# motor5.net
KiCad netlist of a schematic drawn in EAGLE
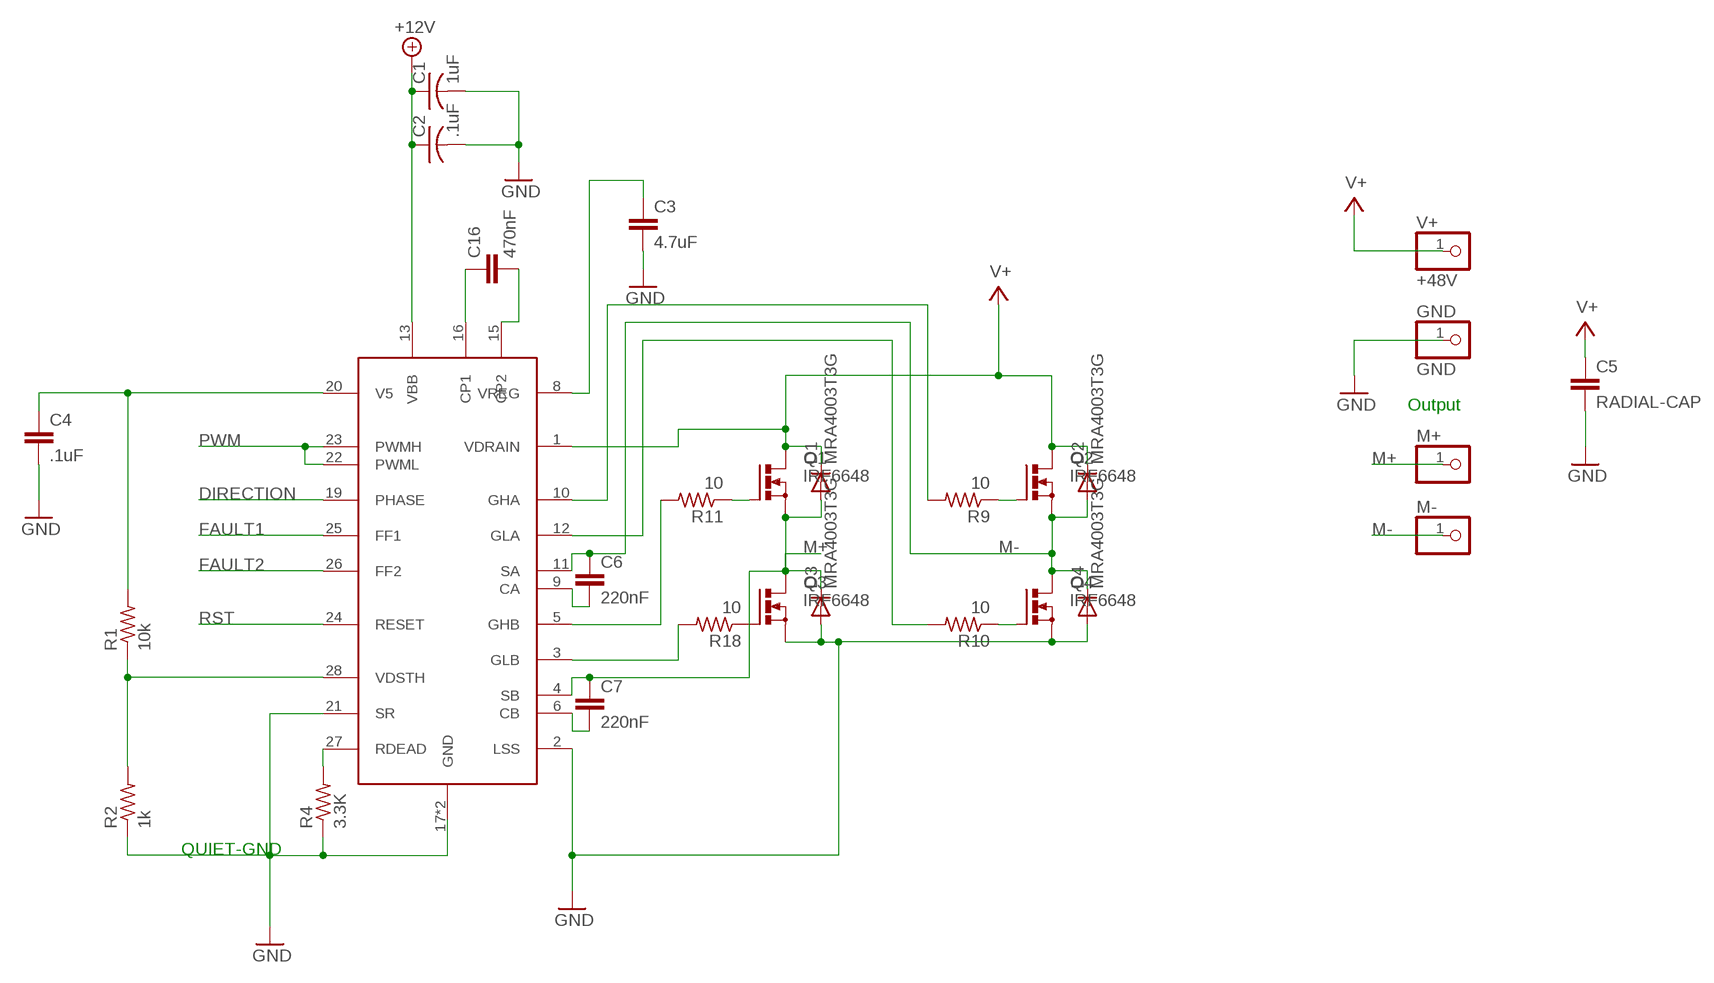
[diagram p0: schematic, sheet 1]
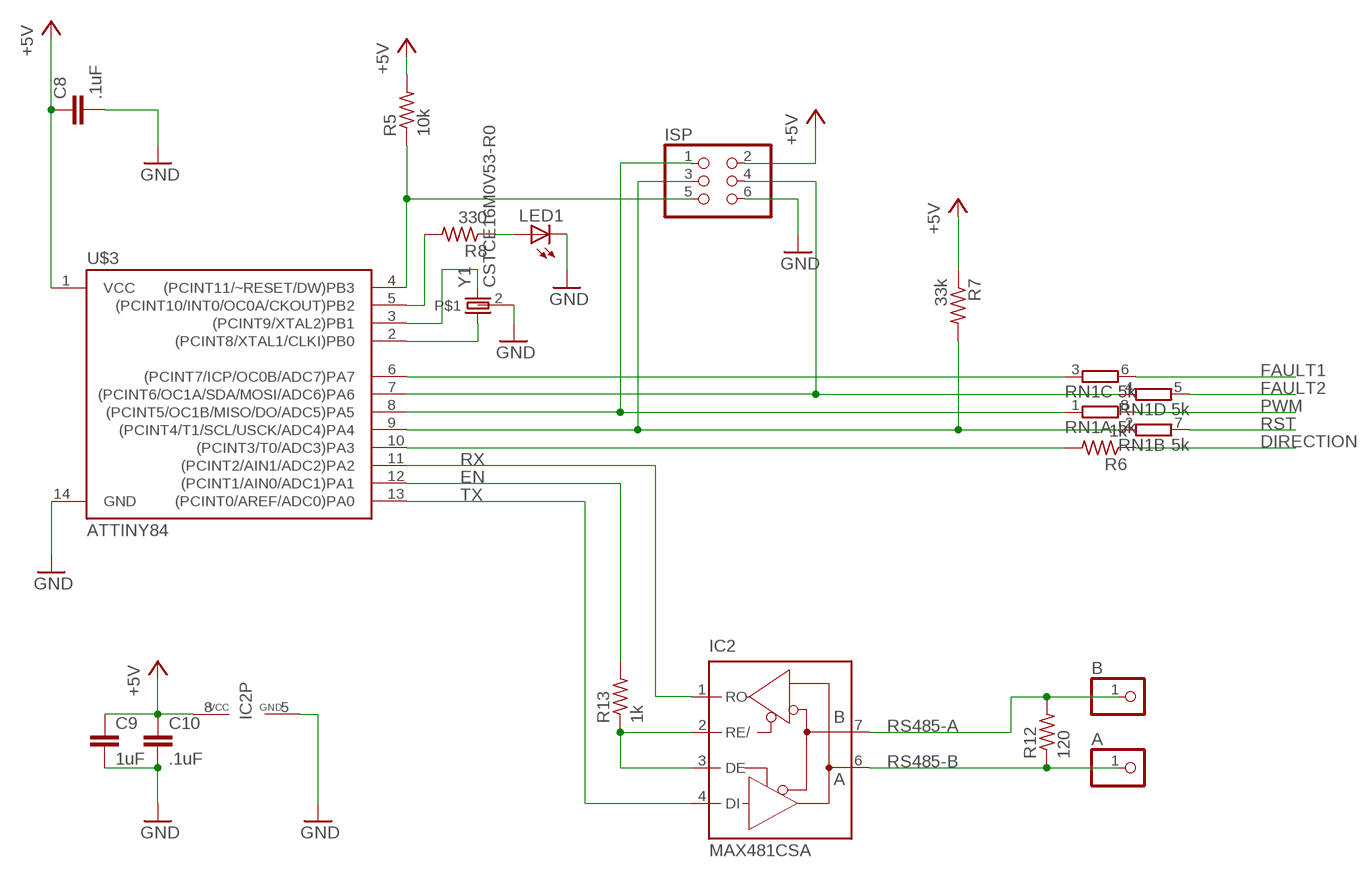
[diagram p1: schematic, sheet 2]
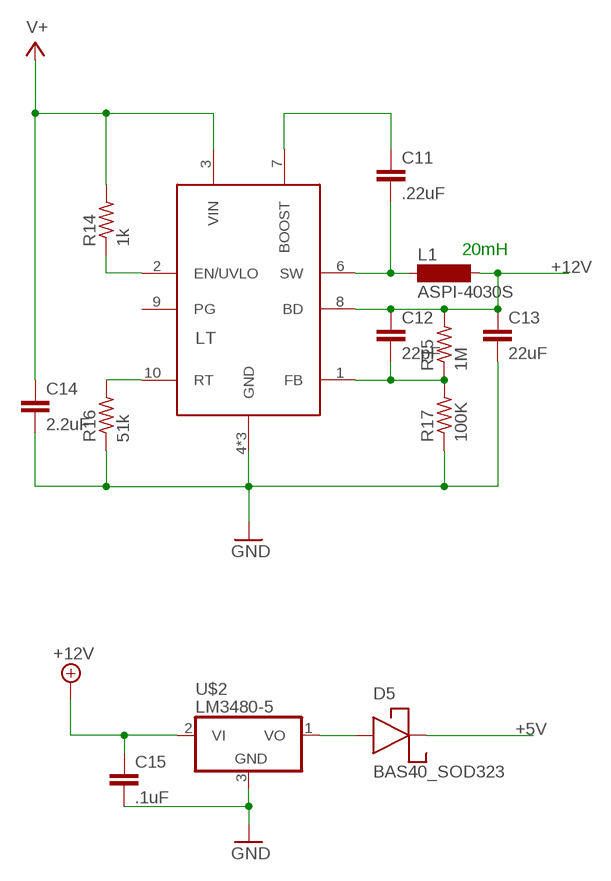
[diagram p2: schematic, sheet 3]

(export (version "E")
  (design (tool "Eeschema 10.0.6"))
  (components
    (comp (ref "C11")
      (value ".22uF")
      (footprint "eagle-import:C0603")
      (libsource (lib "eagle-import") (part "C-EUC0603"))
    )
    (comp (ref "C12")
      (value "22pF")
      (footprint "eagle-import:C0603")
      (libsource (lib "eagle-import") (part "C-EUC0603"))
    )
    (comp (ref "C13")
      (value "22uF")
      (footprint "eagle-import:C0805")
      (libsource (lib "eagle-import") (part "C-EUC0805"))
    )
    (comp (ref "C14")
      (value "2.2uF")
      (footprint "eagle-import:C0603")
      (libsource (lib "eagle-import") (part "C-EUC0603"))
    )
    (comp (ref "C15")
      (value ".1uF")
      (footprint "eagle-import:C0603")
      (libsource (lib "eagle-import") (part "C-EUC0603"))
    )
    (comp (ref "D5")
      (value "BAS40_SOD323")
      (footprint "eagle-import:SOD323")
      (libsource (lib "eagle-import") (part "BAS40_SOD323"))
    )
    (comp (ref "L1")
      (value "ASPI-4030S")
      (footprint "eagle-import:ASPI-4030S")
      (libsource (lib "eagle-import") (part "ASPI-4030S"))
    )
    (comp (ref "LT")
      (value "LT3990")
      (footprint "eagle-import:DFN10-3X3")
      (libsource (lib "eagle-import") (part "LT3990"))
    )
    (comp (ref "R14")
      (value "1k")
      (footprint "eagle-import:R0603")
      (libsource (lib "eagle-import") (part "R-US_R0603"))
    )
    (comp (ref "R15")
      (value "1M")
      (footprint "eagle-import:R0603")
      (libsource (lib "eagle-import") (part "R-US_R0603"))
    )
    (comp (ref "R16")
      (value "51k")
      (footprint "eagle-import:R0603")
      (libsource (lib "eagle-import") (part "R-US_R0603"))
    )
    (comp (ref "R17")
      (value "100K")
      (footprint "eagle-import:R0603")
      (libsource (lib "eagle-import") (part "R-US_R0603"))
    )
    (comp (ref "U$2")
      (value "LM3480-5")
      (footprint "eagle-import:SOT23")
      (libsource (lib "eagle-import") (part "LM3480-5"))
    )
    (comp (ref "A")
      (value "PINHD-1X1")
      (footprint "eagle-import:1X01")
      (libsource (lib "eagle-import") (part "PINHD-1X1"))
    )
    (comp (ref "B")
      (value "PINHD-1X1")
      (footprint "eagle-import:1X01")
      (libsource (lib "eagle-import") (part "PINHD-1X1"))
    )
    (comp (ref "C8")
      (value ".1uF")
      (footprint "eagle-import:C0603")
      (libsource (lib "eagle-import") (part "C-EUC0603"))
    )
    (comp (ref "C9")
      (value "1uF")
      (footprint "eagle-import:C0603")
      (libsource (lib "eagle-import") (part "C-EUC0603"))
    )
    (comp (ref "C10")
      (value ".1uF")
      (footprint "eagle-import:C0603")
      (libsource (lib "eagle-import") (part "C-EUC0603"))
    )
    (comp (ref "IC2")
      (value "MAX481CSA")
      (footprint "eagle-import:SO08")
      (fields (field (name "MF") "MAXIM"))
      (libsource (lib "eagle-import") (part "MAX481CSA"))
    )
    (comp (ref "ISP")
      (value "PINHD-2X3")
      (footprint "eagle-import:2X03")
      (libsource (lib "eagle-import") (part "PINHD-2X3"))
    )
    (comp (ref "LED1")
      (value "LEDCHIPLED_0603")
      (footprint "eagle-import:CHIPLED_0603")
      (libsource (lib "eagle-import") (part "LEDCHIPLED_0603"))
    )
    (comp (ref "R5")
      (value "10k")
      (footprint "eagle-import:R0603")
      (libsource (lib "eagle-import") (part "R-US_R0603"))
    )
    (comp (ref "R6")
      (value "1k")
      (footprint "eagle-import:R0603")
      (libsource (lib "eagle-import") (part "R-US_R0603"))
    )
    (comp (ref "R7")
      (value "33k")
      (footprint "eagle-import:R0603")
      (libsource (lib "eagle-import") (part "R-US_R0603"))
    )
    (comp (ref "R8")
      (value "330")
      (footprint "eagle-import:R0603")
      (libsource (lib "eagle-import") (part "R-US_R0603"))
    )
    (comp (ref "R12")
      (value "120")
      (footprint "eagle-import:R0603")
      (libsource (lib "eagle-import") (part "R-US_R0603"))
    )
    (comp (ref "R13")
      (value "1k")
      (footprint "eagle-import:R0603")
      (libsource (lib "eagle-import") (part "R-US_R0603"))
    )
    (comp (ref "RN1")
      (value "5k")
      (footprint "eagle-import:EXB38V")
      (libsource (lib "eagle-import") (part "4R-NEXB38V"))
    )
    (comp (ref "U$3")
      (value "ATTINY84")
      (footprint "eagle-import:SO14")
      (libsource (lib "eagle-import") (part "ATTINY84"))
    )
    (comp (ref "Y1")
      (value "CSTCE16M0V53-R0")
      (footprint "eagle-import:MYSMD2_RESONATOR")
      (libsource (lib "eagle-import") (part "CSTCE16M0V53-R0"))
    )
    (comp (ref "ALLGR")
      (value "ALLEGRO-A3921")
      (footprint "eagle-import:TSSOP28")
      (libsource (lib "eagle-import") (part "ALLEGRO-A3921"))
    )
    (comp (ref "C1")
      (value "1uF")
      (footprint "eagle-import:C0603")
      (libsource (lib "eagle-import") (part "C-USC0603"))
    )
    (comp (ref "C2")
      (value ".1uF")
      (footprint "eagle-import:C0603")
      (libsource (lib "eagle-import") (part "C-USC0603"))
    )
    (comp (ref "C3")
      (value "4.7uF")
      (footprint "eagle-import:C0603")
      (libsource (lib "eagle-import") (part "C-EUC0603"))
    )
    (comp (ref "C4")
      (value ".1uF")
      (footprint "eagle-import:C0603")
      (libsource (lib "eagle-import") (part "C-EUC0603"))
    )
    (comp (ref "C5")
      (value "RADIAL-CAP")
      (footprint "eagle-import:RADIAL-CAP")
      (libsource (lib "eagle-import") (part "RADIAL-CAP"))
    )
    (comp (ref "C6")
      (value "220nF")
      (footprint "eagle-import:C0603")
      (libsource (lib "eagle-import") (part "C-EUC0603"))
    )
    (comp (ref "C7")
      (value "220nF")
      (footprint "eagle-import:C0603")
      (libsource (lib "eagle-import") (part "C-EUC0603"))
    )
    (comp (ref "C16")
      (value "470nF")
      (footprint "eagle-import:C0603")
      (libsource (lib "eagle-import") (part "C-EUC0603"))
    )
    (comp (ref "D1")
      (value "MRA4003T3G")
      (footprint "eagle-import:SMA")
      (libsource (lib "eagle-import") (part "MRA4003T3G"))
    )
    (comp (ref "D2")
      (value "MRA4003T3G")
      (footprint "eagle-import:SMA")
      (libsource (lib "eagle-import") (part "MRA4003T3G"))
    )
    (comp (ref "D3")
      (value "MRA4003T3G")
      (footprint "eagle-import:SMA")
      (libsource (lib "eagle-import") (part "MRA4003T3G"))
    )
    (comp (ref "D4")
      (value "MRA4003T3G")
      (footprint "eagle-import:SMA")
      (libsource (lib "eagle-import") (part "MRA4003T3G"))
    )
    (comp (ref "GND")
      (value "GND")
      (footprint "eagle-import:1X01")
      (libsource (lib "eagle-import") (part "PINHD-1X1"))
    )
    (comp (ref "M+")
      (value "PINHD-1X1")
      (footprint "eagle-import:1X01")
      (libsource (lib "eagle-import") (part "PINHD-1X1"))
    )
    (comp (ref "M-")
      (value "PINHD-1X1")
      (footprint "eagle-import:1X01")
      (libsource (lib "eagle-import") (part "PINHD-1X1"))
    )
    (comp (ref "Q1")
      (value "IRF6648")
      (footprint "eagle-import:DIRECTFET")
      (libsource (lib "eagle-import") (part "IRF6648"))
    )
    (comp (ref "Q2")
      (value "IRF6648")
      (footprint "eagle-import:DIRECTFET")
      (libsource (lib "eagle-import") (part "IRF6648"))
    )
    (comp (ref "Q3")
      (value "IRF6648")
      (footprint "eagle-import:DIRECTFET")
      (libsource (lib "eagle-import") (part "IRF6648"))
    )
    (comp (ref "Q4")
      (value "IRF6648")
      (footprint "eagle-import:DIRECTFET")
      (libsource (lib "eagle-import") (part "IRF6648"))
    )
    (comp (ref "R1")
      (value "10k")
      (footprint "eagle-import:R0603")
      (libsource (lib "eagle-import") (part "R-US_R0603"))
    )
    (comp (ref "R2")
      (value "1k")
      (footprint "eagle-import:R0603")
      (libsource (lib "eagle-import") (part "R-US_R0603"))
    )
    (comp (ref "R4")
      (value "3.3K")
      (footprint "eagle-import:R0603")
      (libsource (lib "eagle-import") (part "R-US_R0603"))
    )
    (comp (ref "R9")
      (value "10")
      (footprint "eagle-import:R0603")
      (libsource (lib "eagle-import") (part "R-US_R0603"))
    )
    (comp (ref "R10")
      (value "10")
      (footprint "eagle-import:R0603")
      (libsource (lib "eagle-import") (part "R-US_R0603"))
    )
    (comp (ref "R11")
      (value "10")
      (footprint "eagle-import:R0603")
      (libsource (lib "eagle-import") (part "R-US_R0603"))
    )
    (comp (ref "R18")
      (value "10")
      (footprint "eagle-import:R0603")
      (libsource (lib "eagle-import") (part "R-US_R0603"))
    )
    (comp (ref "V+")
      (value "+48V")
      (footprint "eagle-import:1X01")
      (libsource (lib "eagle-import") (part "PINHD-1X1"))
    )
  )
  (nets
    (net (code "1") (name "+5V") (class "Default")
      (node (ref "C10") (pin "1") (pinfunction "1_1") (pintype "passive"))
      (node (ref "C8") (pin "1") (pinfunction "1_1") (pintype "passive"))
      (node (ref "C9") (pin "1") (pinfunction "1_1") (pintype "passive"))
      (node (ref "D5") (pin "1") (pinfunction "P$2_1") (pintype "bidirectional"))
      (node (ref "IC2") (pin "8") (pinfunction "VCC_8") (pintype "power_in"))
      (node (ref "ISP") (pin "2") (pinfunction "2_2") (pintype "passive"))
      (node (ref "R5") (pin "2") (pinfunction "2_2") (pintype "passive"))
      (node (ref "R7") (pin "1") (pinfunction "1_1") (pintype "passive"))
      (node (ref "U$3") (pin "1") (pinfunction "VCC_1") (pintype "bidirectional"))
    )
    (net (code "2") (name "+12V") (class "Default")
      (node (ref "ALLGR") (pin "13") (pinfunction "VBB_13") (pintype "bidirectional"))
      (node (ref "C1") (pin "1") (pinfunction "1_1") (pintype "passive"))
      (node (ref "C12") (pin "1") (pinfunction "1_1") (pintype "passive"))
      (node (ref "C13") (pin "1") (pinfunction "1_1") (pintype "passive"))
      (node (ref "C15") (pin "1") (pinfunction "1_1") (pintype "passive"))
      (node (ref "C2") (pin "1") (pinfunction "1_1") (pintype "passive"))
      (node (ref "L1") (pin "P$2") (pinfunction "2_P$2") (pintype "passive"))
      (node (ref "LT") (pin "8") (pinfunction "BD_8") (pintype "bidirectional"))
      (node (ref "R15") (pin "2") (pinfunction "2_2") (pintype "passive"))
      (node (ref "U$2") (pin "2") (pinfunction "VI_2") (pintype "input"))
    )
    (net (code "3") (name "DIRECTION") (class "Default")
      (node (ref "ALLGR") (pin "19") (pinfunction "PHASE_19") (pintype "bidirectional"))
      (node (ref "R6") (pin "1") (pinfunction "1_1") (pintype "passive"))
    )
    (net (code "4") (name "EN") (class "Default")
      (node (ref "R13") (pin "2") (pinfunction "2_2") (pintype "passive"))
      (node (ref "U$3") (pin "12") (pinfunction "(PCINT1/AIN0/ADC1)PA1_12") (pintype "bidirectional"))
    )
    (net (code "5") (name "FAULT1") (class "Default")
      (node (ref "ALLGR") (pin "25") (pinfunction "FF1_25") (pintype "bidirectional"))
      (node (ref "RN1") (pin "6") (pinfunction "2_6") (pintype "passive"))
    )
    (net (code "6") (name "FAULT2") (class "Default")
      (node (ref "ALLGR") (pin "26") (pinfunction "FF2_26") (pintype "bidirectional"))
      (node (ref "RN1") (pin "5") (pinfunction "2_5") (pintype "passive"))
    )
    (net (code "7") (name "GND") (class "Default")
      (node (ref "ALLGR") (pin "17") (pinfunction "GND_17") (pintype "bidirectional"))
      (node (ref "ALLGR") (pin "2") (pinfunction "LSS_2") (pintype "bidirectional"))
      (node (ref "ALLGR") (pin "21") (pinfunction "SR_21") (pintype "bidirectional"))
      (node (ref "ALLGR") (pin "P$1") (pinfunction "GND_P$1") (pintype "bidirectional"))
      (node (ref "C1") (pin "2") (pinfunction "2_2") (pintype "passive"))
      (node (ref "C10") (pin "2") (pinfunction "2_2") (pintype "passive"))
      (node (ref "C13") (pin "2") (pinfunction "2_2") (pintype "passive"))
      (node (ref "C14") (pin "2") (pinfunction "2_2") (pintype "passive"))
      (node (ref "C15") (pin "2") (pinfunction "2_2") (pintype "passive"))
      (node (ref "C2") (pin "2") (pinfunction "2_2") (pintype "passive"))
      (node (ref "C3") (pin "2") (pinfunction "2_2") (pintype "passive"))
      (node (ref "C4") (pin "2") (pinfunction "2_2") (pintype "passive"))
      (node (ref "C5") (pin "P$2") (pinfunction "2_P$2") (pintype "passive"))
      (node (ref "C8") (pin "2") (pinfunction "2_2") (pintype "passive"))
      (node (ref "C9") (pin "2") (pinfunction "2_2") (pintype "passive"))
      (node (ref "D3") (pin "A") (pinfunction "A_A") (pintype "passive"))
      (node (ref "D4") (pin "A") (pinfunction "A_A") (pintype "passive"))
      (node (ref "GND") (pin "1") (pinfunction "1_1") (pintype "passive"))
      (node (ref "IC2") (pin "5") (pinfunction "GND_5") (pintype "power_in"))
      (node (ref "ISP") (pin "6") (pinfunction "6_6") (pintype "passive"))
      (node (ref "LED1") (pin "C") (pinfunction "C_C") (pintype "passive"))
      (node (ref "LT") (pin "4") (pinfunction "GND_4") (pintype "bidirectional"))
      (node (ref "LT") (pin "5") (pinfunction "GND_5") (pintype "bidirectional"))
      (node (ref "LT") (pin "EXP") (pinfunction "GND_EXP") (pintype "bidirectional"))
      (node (ref "Q3") (pin "S@1") (pinfunction "S_S@1") (pintype "passive"))
      (node (ref "Q3") (pin "S@2") (pinfunction "S_S@2") (pintype "passive"))
      (node (ref "Q4") (pin "S@1") (pinfunction "S_S@1") (pintype "passive"))
      (node (ref "Q4") (pin "S@2") (pinfunction "S_S@2") (pintype "passive"))
      (node (ref "R16") (pin "1") (pinfunction "1_1") (pintype "passive"))
      (node (ref "R17") (pin "1") (pinfunction "1_1") (pintype "passive"))
      (node (ref "R2") (pin "1") (pinfunction "1_1") (pintype "passive"))
      (node (ref "R4") (pin "1") (pinfunction "1_1") (pintype "passive"))
      (node (ref "U$2") (pin "3") (pinfunction "GND_3") (pintype "input"))
      (node (ref "U$3") (pin "14") (pinfunction "GND_14") (pintype "bidirectional"))
      (node (ref "Y1") (pin "2") (pinfunction "P$1_2") (pintype "bidirectional"))
    )
    (net (code "8") (name "M+") (class "Default")
      (node (ref "ALLGR") (pin "4") (pinfunction "SB_4") (pintype "bidirectional"))
      (node (ref "C7") (pin "1") (pinfunction "1_1") (pintype "passive"))
      (node (ref "D1") (pin "A") (pinfunction "A_A") (pintype "passive"))
      (node (ref "D3") (pin "C") (pinfunction "C_C") (pintype "passive"))
      (node (ref "M+") (pin "1") (pinfunction "1_1") (pintype "passive"))
      (node (ref "Q1") (pin "S@1") (pinfunction "S_S@1") (pintype "passive"))
      (node (ref "Q1") (pin "S@2") (pinfunction "S_S@2") (pintype "passive"))
      (node (ref "Q3") (pin "D@1") (pinfunction "D_D@1") (pintype "passive"))
      (node (ref "Q3") (pin "D@2") (pinfunction "D_D@2") (pintype "passive"))
      (node (ref "Q3") (pin "D@3") (pinfunction "D_D@3") (pintype "passive"))
      (node (ref "Q3") (pin "D@4") (pinfunction "D_D@4") (pintype "passive"))
    )
    (net (code "9") (name "M-") (class "Default")
      (node (ref "ALLGR") (pin "11") (pinfunction "SA_11") (pintype "bidirectional"))
      (node (ref "C6") (pin "1") (pinfunction "1_1") (pintype "passive"))
      (node (ref "D2") (pin "A") (pinfunction "A_A") (pintype "passive"))
      (node (ref "D4") (pin "C") (pinfunction "C_C") (pintype "passive"))
      (node (ref "M-") (pin "1") (pinfunction "1_1") (pintype "passive"))
      (node (ref "Q2") (pin "S@1") (pinfunction "S_S@1") (pintype "passive"))
      (node (ref "Q2") (pin "S@2") (pinfunction "S_S@2") (pintype "passive"))
      (node (ref "Q4") (pin "D@1") (pinfunction "D_D@1") (pintype "passive"))
      (node (ref "Q4") (pin "D@2") (pinfunction "D_D@2") (pintype "passive"))
      (node (ref "Q4") (pin "D@3") (pinfunction "D_D@3") (pintype "passive"))
      (node (ref "Q4") (pin "D@4") (pinfunction "D_D@4") (pintype "passive"))
    )
    (net (code "10") (name "Net-(ALLGR-CA)") (class "Default")
      (node (ref "ALLGR") (pin "9") (pinfunction "CA_9") (pintype "bidirectional"))
      (node (ref "C6") (pin "2") (pinfunction "2_2") (pintype "passive"))
    )
    (net (code "11") (name "Net-(ALLGR-CB)") (class "Default")
      (node (ref "ALLGR") (pin "6") (pinfunction "CB_6") (pintype "bidirectional"))
      (node (ref "C7") (pin "2") (pinfunction "2_2") (pintype "passive"))
    )
    (net (code "12") (name "Net-(ALLGR-CP1)") (class "Default")
      (node (ref "ALLGR") (pin "16") (pinfunction "CP1_16") (pintype "bidirectional"))
      (node (ref "C16") (pin "1") (pinfunction "1_1") (pintype "passive"))
    )
    (net (code "13") (name "Net-(ALLGR-CP2)") (class "Default")
      (node (ref "ALLGR") (pin "15") (pinfunction "CP2_15") (pintype "bidirectional"))
      (node (ref "C16") (pin "2") (pinfunction "2_2") (pintype "passive"))
    )
    (net (code "14") (name "Net-(ALLGR-GHA)") (class "Default")
      (node (ref "ALLGR") (pin "10") (pinfunction "GHA_10") (pintype "bidirectional"))
      (node (ref "R9") (pin "2") (pinfunction "2_2") (pintype "passive"))
    )
    (net (code "15") (name "Net-(ALLGR-GHB)") (class "Default")
      (node (ref "ALLGR") (pin "5") (pinfunction "GHB_5") (pintype "bidirectional"))
      (node (ref "R11") (pin "2") (pinfunction "2_2") (pintype "passive"))
    )
    (net (code "16") (name "Net-(ALLGR-GLA)") (class "Default")
      (node (ref "ALLGR") (pin "12") (pinfunction "GLA_12") (pintype "bidirectional"))
      (node (ref "R10") (pin "2") (pinfunction "2_2") (pintype "passive"))
    )
    (net (code "17") (name "Net-(ALLGR-GLB)") (class "Default")
      (node (ref "ALLGR") (pin "3") (pinfunction "GLB_3") (pintype "bidirectional"))
      (node (ref "R18") (pin "2") (pinfunction "2_2") (pintype "passive"))
    )
    (net (code "18") (name "Net-(ALLGR-RDEAD)") (class "Default")
      (node (ref "ALLGR") (pin "27") (pinfunction "RDEAD_27") (pintype "bidirectional"))
      (node (ref "R4") (pin "2") (pinfunction "2_2") (pintype "passive"))
    )
    (net (code "19") (name "Net-(ALLGR-V5)") (class "Default")
      (node (ref "ALLGR") (pin "20") (pinfunction "V5_20") (pintype "bidirectional"))
      (node (ref "C4") (pin "1") (pinfunction "1_1") (pintype "passive"))
      (node (ref "R1") (pin "2") (pinfunction "2_2") (pintype "passive"))
    )
    (net (code "20") (name "Net-(ALLGR-VDSTH)") (class "Default")
      (node (ref "ALLGR") (pin "28") (pinfunction "VDSTH_28") (pintype "bidirectional"))
      (node (ref "R1") (pin "1") (pinfunction "1_1") (pintype "passive"))
      (node (ref "R2") (pin "2") (pinfunction "2_2") (pintype "passive"))
    )
    (net (code "21") (name "Net-(ALLGR-VREG)") (class "Default")
      (node (ref "ALLGR") (pin "8") (pinfunction "VREG_8") (pintype "bidirectional"))
      (node (ref "C3") (pin "1") (pinfunction "1_1") (pintype "passive"))
    )
    (net (code "22") (name "Net-(D5-P$1)") (class "Default")
      (node (ref "D5") (pin "2") (pinfunction "P$1_2") (pintype "bidirectional"))
      (node (ref "U$2") (pin "1") (pinfunction "VO_1") (pintype "passive"))
    )
    (net (code "23") (name "Net-(IC2A-DE)") (class "Default")
      (node (ref "IC2") (pin "2") (pinfunction "RE/_2") (pintype "input"))
      (node (ref "IC2") (pin "3") (pinfunction "DE_3") (pintype "input"))
      (node (ref "R13") (pin "1") (pinfunction "1_1") (pintype "passive"))
    )
    (net (code "24") (name "Net-(L1-1)") (class "Default")
      (node (ref "C11") (pin "2") (pinfunction "2_2") (pintype "passive"))
      (node (ref "L1") (pin "P$1") (pinfunction "1_P$1") (pintype "passive"))
      (node (ref "LT") (pin "6") (pinfunction "SW_6") (pintype "bidirectional"))
    )
    (net (code "25") (name "Net-(LED1-PadA)") (class "Default")
      (node (ref "LED1") (pin "A") (pinfunction "A_A") (pintype "passive"))
      (node (ref "R8") (pin "1") (pinfunction "1_1") (pintype "passive"))
    )
    (net (code "26") (name "Net-(LT-BOOST)") (class "Default")
      (node (ref "C11") (pin "1") (pinfunction "1_1") (pintype "passive"))
      (node (ref "LT") (pin "7") (pinfunction "BOOST_7") (pintype "bidirectional"))
    )
    (net (code "27") (name "Net-(LT-EN{slash}UVLO)") (class "Default")
      (node (ref "LT") (pin "2") (pinfunction "EN/UVLO_2") (pintype "bidirectional"))
      (node (ref "R14") (pin "1") (pinfunction "1_1") (pintype "passive"))
    )
    (net (code "28") (name "Net-(LT-FB)") (class "Default")
      (node (ref "C12") (pin "2") (pinfunction "2_2") (pintype "passive"))
      (node (ref "LT") (pin "1") (pinfunction "FB_1") (pintype "bidirectional"))
      (node (ref "R15") (pin "1") (pinfunction "1_1") (pintype "passive"))
      (node (ref "R17") (pin "2") (pinfunction "2_2") (pintype "passive"))
    )
    (net (code "29") (name "Net-(LT-RT)") (class "Default")
      (node (ref "LT") (pin "10") (pinfunction "RT_10") (pintype "bidirectional"))
      (node (ref "R16") (pin "2") (pinfunction "2_2") (pintype "passive"))
    )
    (net (code "30") (name "Net-(Q1-PadG)") (class "Default")
      (node (ref "Q1") (pin "G") (pinfunction "G_G") (pintype "passive"))
      (node (ref "R11") (pin "1") (pinfunction "1_1") (pintype "passive"))
    )
    (net (code "31") (name "Net-(Q2-PadG)") (class "Default")
      (node (ref "Q2") (pin "G") (pinfunction "G_G") (pintype "passive"))
      (node (ref "R9") (pin "1") (pinfunction "1_1") (pintype "passive"))
    )
    (net (code "32") (name "Net-(Q3-PadG)") (class "Default")
      (node (ref "Q3") (pin "G") (pinfunction "G_G") (pintype "passive"))
      (node (ref "R18") (pin "1") (pinfunction "1_1") (pintype "passive"))
    )
    (net (code "33") (name "Net-(Q4-PadG)") (class "Default")
      (node (ref "Q4") (pin "G") (pinfunction "G_G") (pintype "passive"))
      (node (ref "R10") (pin "1") (pinfunction "1_1") (pintype "passive"))
    )
    (net (code "34") (name "Net-(RN1B-1)") (class "Default")
      (node (ref "ISP") (pin "3") (pinfunction "3_3") (pintype "passive"))
      (node (ref "R7") (pin "2") (pinfunction "2_2") (pintype "passive"))
      (node (ref "RN1") (pin "2") (pinfunction "1_2") (pintype "passive"))
      (node (ref "U$3") (pin "9") (pinfunction "(PCINT4/T1/SCL/USCK/ADC4)PA4_9") (pintype "bidirectional"))
    )
    (net (code "35") (name "Net-(RN1C-1)") (class "Default")
      (node (ref "RN1") (pin "3") (pinfunction "1_3") (pintype "passive"))
      (node (ref "U$3") (pin "6") (pinfunction "(PCINT7/ICP/OC0B/ADC7)PA7_6") (pintype "bidirectional"))
    )
    (net (code "36") (name "Net-(RN1D-1)") (class "Default")
      (node (ref "ISP") (pin "4") (pinfunction "4_4") (pintype "passive"))
      (node (ref "RN1") (pin "4") (pinfunction "1_4") (pintype "passive"))
      (node (ref "U$3") (pin "7") (pinfunction "(PCINT6/OC1A/SDA/MOSI/ADC6)PA6_7") (pintype "bidirectional"))
    )
    (net (code "37") (name "Net-(U$3-(PCINT3{slash}T0{slash}ADC3)PA3)") (class "Default")
      (node (ref "R6") (pin "2") (pinfunction "2_2") (pintype "passive"))
      (node (ref "U$3") (pin "10") (pinfunction "(PCINT3/T0/ADC3)PA3_10") (pintype "bidirectional"))
    )
    (net (code "38") (name "Net-(U$3-(PCINT5{slash}OC1B{slash}MISO{slash}DO{slash}ADC5)PA5)") (class "Default")
      (node (ref "ISP") (pin "1") (pinfunction "1_1") (pintype "passive"))
      (node (ref "RN1") (pin "1") (pinfunction "1_1") (pintype "passive"))
      (node (ref "U$3") (pin "8") (pinfunction "(PCINT5/OC1B/MISO/DO/ADC5)PA5_8") (pintype "bidirectional"))
    )
    (net (code "39") (name "Net-(U$3-(PCINT8{slash}XTAL1{slash}CLKI)PB0)") (class "Default")
      (node (ref "U$3") (pin "2") (pinfunction "(PCINT8/XTAL1/CLKI)PB0_2") (pintype "bidirectional"))
      (node (ref "Y1") (pin "1") (pinfunction "1_1") (pintype "passive"))
    )
    (net (code "40") (name "Net-(U$3-(PCINT9{slash}XTAL2)PB1)") (class "Default")
      (node (ref "U$3") (pin "3") (pinfunction "(PCINT9/XTAL2)PB1_3") (pintype "bidirectional"))
      (node (ref "Y1") (pin "3") (pinfunction "2_3") (pintype "passive"))
    )
    (net (code "41") (name "Net-(U$3-(PCINT10{slash}INT0{slash}OC0A{slash}CKOUT)PB2)") (class "Default")
      (node (ref "R8") (pin "2") (pinfunction "2_2") (pintype "passive"))
      (node (ref "U$3") (pin "5") (pinfunction "(PCINT10/INT0/OC0A/CKOUT)PB2_5") (pintype "bidirectional"))
    )
    (net (code "42") (name "Net-(U$3-(PCINT11{slash}~{RESET{slash}DW})PB3)") (class "Default")
      (node (ref "ISP") (pin "5") (pinfunction "5_5") (pintype "passive"))
      (node (ref "R5") (pin "1") (pinfunction "1_1") (pintype "passive"))
      (node (ref "U$3") (pin "4") (pinfunction "(PCINT11/~{RESET/DW})PB3_4") (pintype "bidirectional"))
    )
    (net (code "43") (name "PWM") (class "Default")
      (node (ref "ALLGR") (pin "22") (pinfunction "PWML_22") (pintype "bidirectional"))
      (node (ref "ALLGR") (pin "23") (pinfunction "PWMH_23") (pintype "bidirectional"))
      (node (ref "RN1") (pin "8") (pinfunction "2_8") (pintype "passive"))
    )
    (net (code "44") (name "RS485-A") (class "Default")
      (node (ref "B") (pin "1") (pinfunction "1_1") (pintype "passive"))
      (node (ref "IC2") (pin "7") (pinfunction "B_7") (pintype "passive"))
      (node (ref "R12") (pin "2") (pinfunction "2_2") (pintype "passive"))
    )
    (net (code "45") (name "RS485-B") (class "Default")
      (node (ref "A") (pin "1") (pinfunction "1_1") (pintype "passive"))
      (node (ref "IC2") (pin "6") (pinfunction "A_6") (pintype "passive"))
      (node (ref "R12") (pin "1") (pinfunction "1_1") (pintype "passive"))
    )
    (net (code "46") (name "RST") (class "Default")
      (node (ref "ALLGR") (pin "24") (pinfunction "RESET_24") (pintype "bidirectional"))
      (node (ref "RN1") (pin "7") (pinfunction "2_7") (pintype "passive"))
    )
    (net (code "47") (name "RX") (class "Default")
      (node (ref "IC2") (pin "1") (pinfunction "RO_1") (pintype "output"))
      (node (ref "U$3") (pin "11") (pinfunction "(PCINT2/AIN1/ADC2)PA2_11") (pintype "bidirectional"))
    )
    (net (code "48") (name "TX") (class "Default")
      (node (ref "IC2") (pin "4") (pinfunction "DI_4") (pintype "input"))
      (node (ref "U$3") (pin "13") (pinfunction "(PCINT0/AREF/ADC0)PA0_13") (pintype "bidirectional"))
    )
    (net (code "49") (name "V+") (class "Default")
      (node (ref "ALLGR") (pin "1") (pinfunction "VDRAIN_1") (pintype "bidirectional"))
      (node (ref "C14") (pin "1") (pinfunction "1_1") (pintype "passive"))
      (node (ref "C5") (pin "P$1") (pinfunction "1_P$1") (pintype "passive"))
      (node (ref "D1") (pin "C") (pinfunction "C_C") (pintype "passive"))
      (node (ref "D2") (pin "C") (pinfunction "C_C") (pintype "passive"))
      (node (ref "LT") (pin "3") (pinfunction "VIN_3") (pintype "bidirectional"))
      (node (ref "Q1") (pin "D@1") (pinfunction "D_D@1") (pintype "passive"))
      (node (ref "Q1") (pin "D@2") (pinfunction "D_D@2") (pintype "passive"))
      (node (ref "Q1") (pin "D@3") (pinfunction "D_D@3") (pintype "passive"))
      (node (ref "Q1") (pin "D@4") (pinfunction "D_D@4") (pintype "passive"))
      (node (ref "Q2") (pin "D@1") (pinfunction "D_D@1") (pintype "passive"))
      (node (ref "Q2") (pin "D@2") (pinfunction "D_D@2") (pintype "passive"))
      (node (ref "Q2") (pin "D@3") (pinfunction "D_D@3") (pintype "passive"))
      (node (ref "Q2") (pin "D@4") (pinfunction "D_D@4") (pintype "passive"))
      (node (ref "R14") (pin "2") (pinfunction "2_2") (pintype "passive"))
      (node (ref "V+") (pin "1") (pinfunction "1_1") (pintype "passive"))
    )
    (net (code "50") (name "unconnected-(LT-PG-Pad9)") (class "Default")
      (node (ref "LT") (pin "9") (pinfunction "PG_9") (pintype "bidirectional"))
    )
  )
)
